# Endstops.net
KiCad netlist of a schematic drawn in Altium Designer
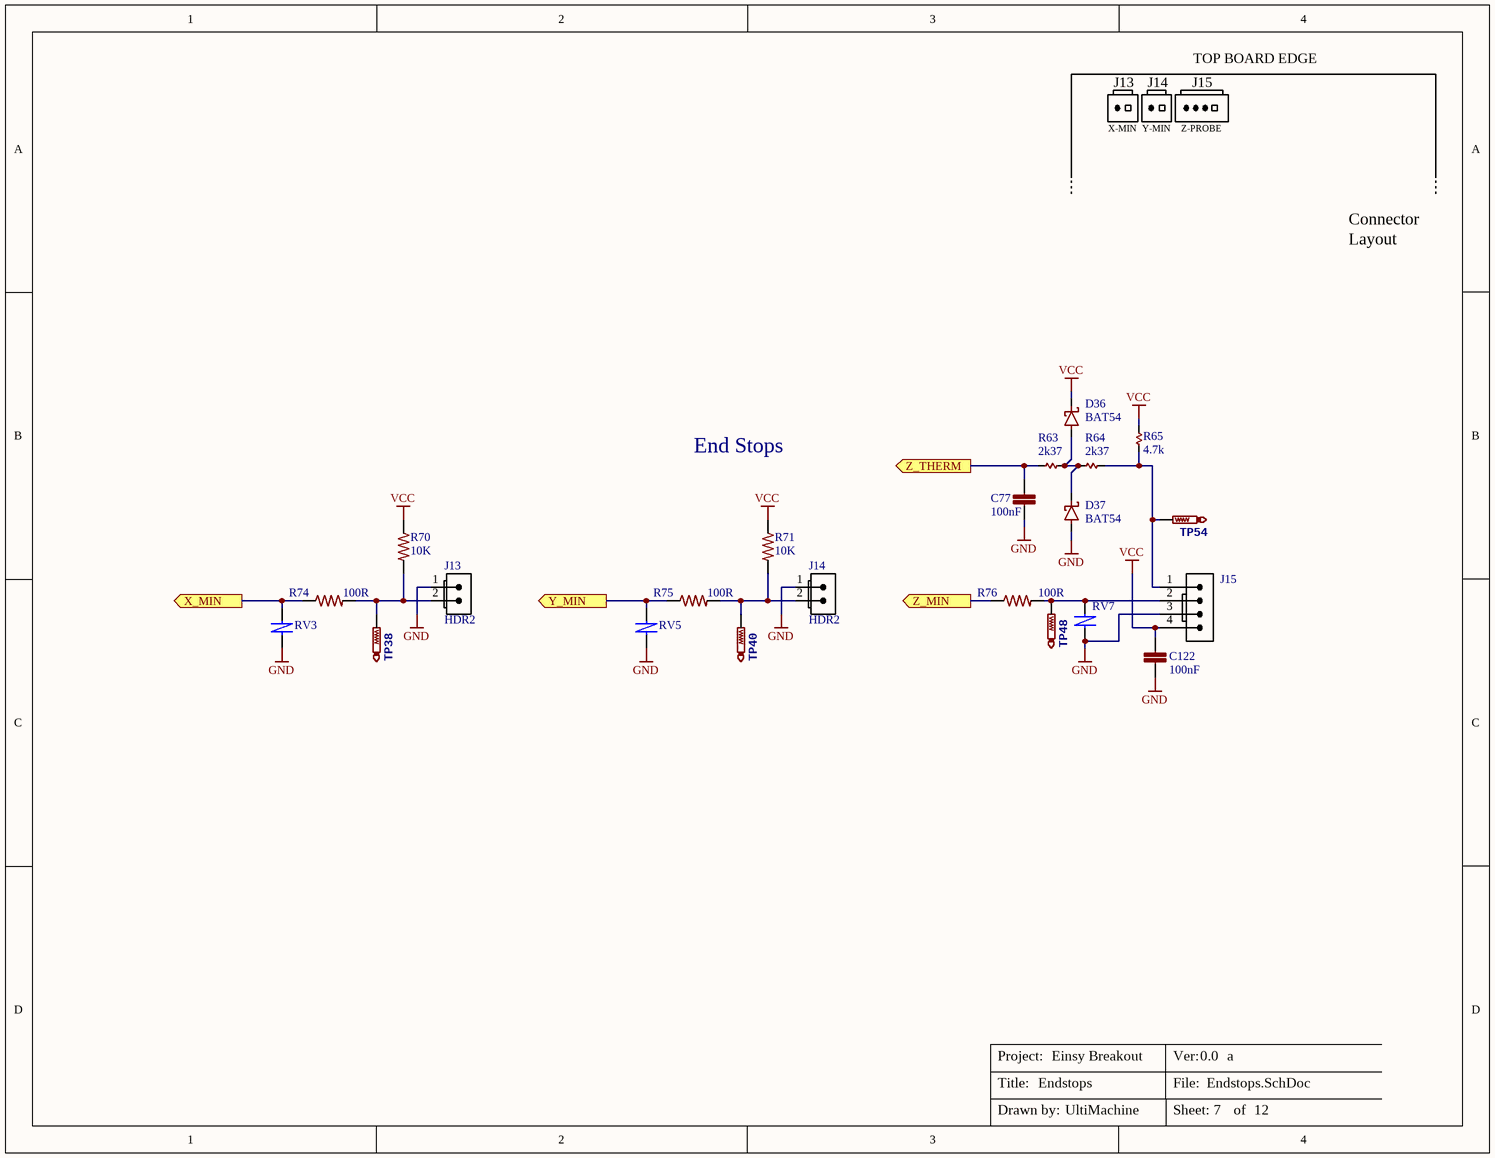
[diagram p0: Endstops.SchDoc]

(export (version "E")
  (design (tool "Eeschema 10.0.6"))
  (components
    (comp (ref "C77")
      (value "100nF")
      (footprint "C0402")
      (description "CAP CER 0402 100nF 16V 10% X7R")
      (fields (field (name "MANUFACTURER") "Murata") (field (name "TOLERANCE") "+/- 10%"))
      (libsource (lib "") (part "GRM155R71C104KA88D_1"))
    )
    (comp (ref "C122")
      (value "100nF")
      (footprint "C0402")
      (description "CAP CER 0402 100nF 16V 10% X7R")
      (fields (field (name "MANUFACTURER") "Murata") (field (name "TOLERANCE") "+/- 10%"))
      (libsource (lib "3Delight") (part "GRM155R71C104KA88D"))
    )
    (comp (ref "D36")
      (value "BAT54")
      (footprint "SOD523_IPC")
      (description "Diode Schottky 30V 100mA Surface Mount SOD-523")
      (fields (field (name "MANUFACTURER") "Diodes Incorporated") (field (name "TOLERANCE") "NA"))
      (libsource (lib "3Delight") (part "BAT54WT-7"))
    )
    (comp (ref "D37")
      (value "BAT54")
      (footprint "SOD523_IPC")
      (description "Diode Schottky 30V 100mA Surface Mount SOD-523")
      (fields (field (name "MANUFACTURER") "Diodes Incorporated") (field (name "TOLERANCE") "NA"))
      (libsource (lib "3Delight") (part "BAT54WT-7"))
    )
    (comp (ref "J13")
      (value "HDR2")
      (footprint "70543-02")
      (description "Connector 2pos")
      (fields (field (name "MANUFACTURER") "Molex") (field (name "PART") "10 Pin Conn"))
      (libsource (lib "Archim_0.4") (part "CONN 2PIN VERT 0.1{dblquote} SHRD LOCKING"))
    )
    (comp (ref "J14")
      (value "HDR2")
      (footprint "70543-02")
      (description "Connector 2pos")
      (fields (field (name "MANUFACTURER") "Molex") (field (name "PART") "10 Pin Conn"))
      (libsource (lib "Archim_0.4") (part "CONN 2PIN VERT 0.1{dblquote} SHRD LOCKING"))
    )
    (comp (ref "J15")
      (value "Molex 0705430003")
      (footprint "4POL254")
      (description "Molex 4 Pin Clip Connector")
      (fields (field (name "MANUFACTURER") "Molex") (field (name "PART") "4 Pin Conn"))
      (libsource (lib "3Delight") (part "CONN 4PIN 0.1{dblquote} VERT SHRD LOCK ALT"))
    )
    (comp (ref "R63")
      (value "2k37")
      (footprint "R0402")
      (description "RES SMD 2.37K OHM 1% 1/16W 0402")
      (fields (field (name "MANUFACTURER") "Yageo") (field (name "PART") "2.37k"))
      (libsource (lib "3Delight") (part "RC0402FR-072K37L"))
    )
    (comp (ref "R64")
      (value "2k37")
      (footprint "R0402")
      (description "RES SMD 2.37K OHM 1% 1/16W 0402")
      (fields (field (name "MANUFACTURER") "Yageo") (field (name "PART") "2.37k"))
      (libsource (lib "3Delight") (part "RC0402FR-072K37L"))
    )
    (comp (ref "R65")
      (value "4.7k")
      (footprint "R0402")
      (description "RES SMD 4.7K OHM 1% 1/16W 0402")
      (fields (field (name "MANUFACTURER") "Yageo") (field (name "TOLERANCE") "+/- 1%"))
      (libsource (lib "3Delight") (part "RC0402FR-074K7L"))
    )
    (comp (ref "R70")
      (value "10K")
      (footprint "R0402")
      (description "RES SMD 10K OHM 1% 1/16W 0402")
      (fields (field (name "MANUFACTURER") "Yageo") (field (name "PART") "10k 1% 0402"))
      (libsource (lib "3Delight") (part "RC0402FR-0710KP"))
    )
    (comp (ref "R71")
      (value "10K")
      (footprint "R0402")
      (description "RES SMD 10K OHM 1% 1/16W 0402")
      (fields (field (name "MANUFACTURER") "Yageo") (field (name "PART") "10k 1% 0402"))
      (libsource (lib "3Delight") (part "RC0402FR-0710KP"))
    )
    (comp (ref "R74")
      (value "100R")
      (footprint "R0402")
      (description "RES SMD 100 OHM 1% 1/16W 0402")
      (fields (field (name "MANUFACTURER") "Yageo") (field (name "PART") "100R 1% 0402"))
      (libsource (lib "Archim") (part "RES 100R 0402 1%"))
    )
    (comp (ref "R75")
      (value "100R")
      (footprint "R0402")
      (description "RES SMD 100 OHM 1% 1/16W 0402")
      (fields (field (name "MANUFACTURER") "Yageo") (field (name "PART") "100R 1% 0402"))
      (libsource (lib "Archim") (part "RES 100R 0402 1%"))
    )
    (comp (ref "R76")
      (value "100R")
      (footprint "R0402")
      (description "RES SMD 100 OHM 1% 1/16W 0402")
      (fields (field (name "MANUFACTURER") "Yageo") (field (name "PART") "100R 1% 0402"))
      (libsource (lib "Archim") (part "RES 100R 0402 1%"))
    )
    (comp (ref "RV3")
      (value "VRS0402SR55R101N")
      (footprint "C0402")
      (description "Multi-Layer Varistor")
      (fields (field (name "MANUFACTURER") "Yageo") (field (name "PART") "12V"))
      (libsource (lib "3Delight") (part "VRS0402SR55R101N"))
    )
    (comp (ref "RV5")
      (value "VRS0402SR55R101N")
      (footprint "C0402")
      (description "Multi-Layer Varistor")
      (fields (field (name "MANUFACTURER") "Yageo") (field (name "PART") "12V"))
      (libsource (lib "3Delight") (part "VRS0402SR55R101N"))
    )
    (comp (ref "RV7")
      (value "VRS0402SR55R101N")
      (footprint "C0402")
      (description "Multi-Layer Varistor")
      (fields (field (name "MANUFACTURER") "Yageo") (field (name "PART") "12V"))
      (libsource (lib "3Delight") (part "VRS0402SR55R101N"))
    )
    (comp (ref "TP38")
      (value "TestPoint")
      (footprint "TP1-27")
      (description "Test Point")
      (libsource (lib "3Delight") (part "TestPoint"))
    )
    (comp (ref "TP40")
      (value "TestPoint")
      (footprint "TP1-27")
      (description "Test Point")
      (libsource (lib "3Delight") (part "TestPoint"))
    )
    (comp (ref "TP48")
      (value "TestPoint")
      (footprint "TP1-27")
      (description "Test Point")
      (libsource (lib "3Delight") (part "TestPoint"))
    )
    (comp (ref "TP54")
      (value "TestPoint")
      (footprint "TP1-27")
      (description "Test Point")
      (libsource (lib "") (part "TestPoint_1"))
    )
  )
  (nets
    (net (code "1") (name "/X_MIN") (class "Default")
      (node (ref "R74") (pin "1") (pinfunction "1_1") (pintype "passive"))
      (node (ref "RV3") (pin "2") (pinfunction "2_2") (pintype "passive"))
    )
    (net (code "2") (name "/Y_MIN") (class "Default")
      (node (ref "R75") (pin "1") (pinfunction "1_1") (pintype "passive"))
      (node (ref "RV5") (pin "2") (pinfunction "2_2") (pintype "passive"))
    )
    (net (code "3") (name "/Z_MIN") (class "Default")
      (node (ref "R76") (pin "1") (pinfunction "1_1") (pintype "passive"))
    )
    (net (code "4") (name "/Z_THERM") (class "Default")
      (node (ref "C77") (pin "1") (pinfunction "1_1") (pintype "passive"))
      (node (ref "R63") (pin "2") (pinfunction "2_2") (pintype "passive"))
    )
    (net (code "5") (name "GND") (class "Default")
      (node (ref "C122") (pin "1") (pinfunction "1_1") (pintype "passive"))
      (node (ref "C77") (pin "2") (pinfunction "2_2") (pintype "passive"))
      (node (ref "D37") (pin "A") (pinfunction "A_A") (pintype "passive"))
      (node (ref "J13") (pin "1") (pinfunction "S_1") (pintype "passive"))
      (node (ref "J14") (pin "1") (pinfunction "S_1") (pintype "passive"))
      (node (ref "J15") (pin "3") (pinfunction "3_3") (pintype "passive"))
      (node (ref "RV3") (pin "1") (pinfunction "1_1") (pintype "passive"))
      (node (ref "RV5") (pin "1") (pinfunction "1_1") (pintype "passive"))
      (node (ref "RV7") (pin "1") (pinfunction "1_1") (pintype "passive"))
    )
    (net (code "6") (name "Net-(D36-PadA)") (class "Default")
      (node (ref "D36") (pin "A") (pinfunction "A_A") (pintype "passive"))
      (node (ref "D37") (pin "K") (pinfunction "K_K") (pintype "passive"))
      (node (ref "R63") (pin "1") (pinfunction "1_1") (pintype "passive"))
      (node (ref "R64") (pin "2") (pinfunction "2_2") (pintype "passive"))
    )
    (net (code "7") (name "Net-(J13-S-Pad2)") (class "Default")
      (node (ref "J13") (pin "2") (pinfunction "S_2") (pintype "passive"))
      (node (ref "R70") (pin "2") (pinfunction "2_2") (pintype "passive"))
      (node (ref "R74") (pin "2") (pinfunction "2_2") (pintype "passive"))
      (node (ref "TP38") (pin "TP") (pinfunction "TP_TP") (pintype "passive"))
    )
    (net (code "8") (name "Net-(J14-S-Pad2)") (class "Default")
      (node (ref "J14") (pin "2") (pinfunction "S_2") (pintype "passive"))
      (node (ref "R71") (pin "2") (pinfunction "2_2") (pintype "passive"))
      (node (ref "R75") (pin "2") (pinfunction "2_2") (pintype "passive"))
      (node (ref "TP40") (pin "TP") (pinfunction "TP_TP") (pintype "passive"))
    )
    (net (code "9") (name "Net-(J15-Pad1)") (class "Default")
      (node (ref "J15") (pin "1") (pinfunction "1_1") (pintype "passive"))
      (node (ref "R64") (pin "1") (pinfunction "1_1") (pintype "passive"))
      (node (ref "R65") (pin "1") (pinfunction "1_1") (pintype "passive"))
      (node (ref "TP54") (pin "TP") (pinfunction "TP_TP") (pintype "passive"))
    )
    (net (code "10") (name "Net-(J15-Pad2)") (class "Default")
      (node (ref "J15") (pin "2") (pinfunction "2_2") (pintype "passive"))
      (node (ref "R76") (pin "2") (pinfunction "2_2") (pintype "passive"))
      (node (ref "RV7") (pin "2") (pinfunction "2_2") (pintype "passive"))
      (node (ref "TP48") (pin "TP") (pinfunction "TP_TP") (pintype "passive"))
    )
    (net (code "11") (name "VCC") (class "Default")
      (node (ref "C122") (pin "2") (pinfunction "2_2") (pintype "passive"))
      (node (ref "D36") (pin "K") (pinfunction "K_K") (pintype "passive"))
      (node (ref "J15") (pin "4") (pinfunction "4_4") (pintype "passive"))
      (node (ref "R65") (pin "2") (pinfunction "2_2") (pintype "passive"))
      (node (ref "R70") (pin "1") (pinfunction "1_1") (pintype "passive"))
      (node (ref "R71") (pin "1") (pinfunction "1_1") (pintype "passive"))
    )
  )
)
